# SCH_teency_2021-08-24.net
KiCad netlist of a schematic drawn in EasyEDA
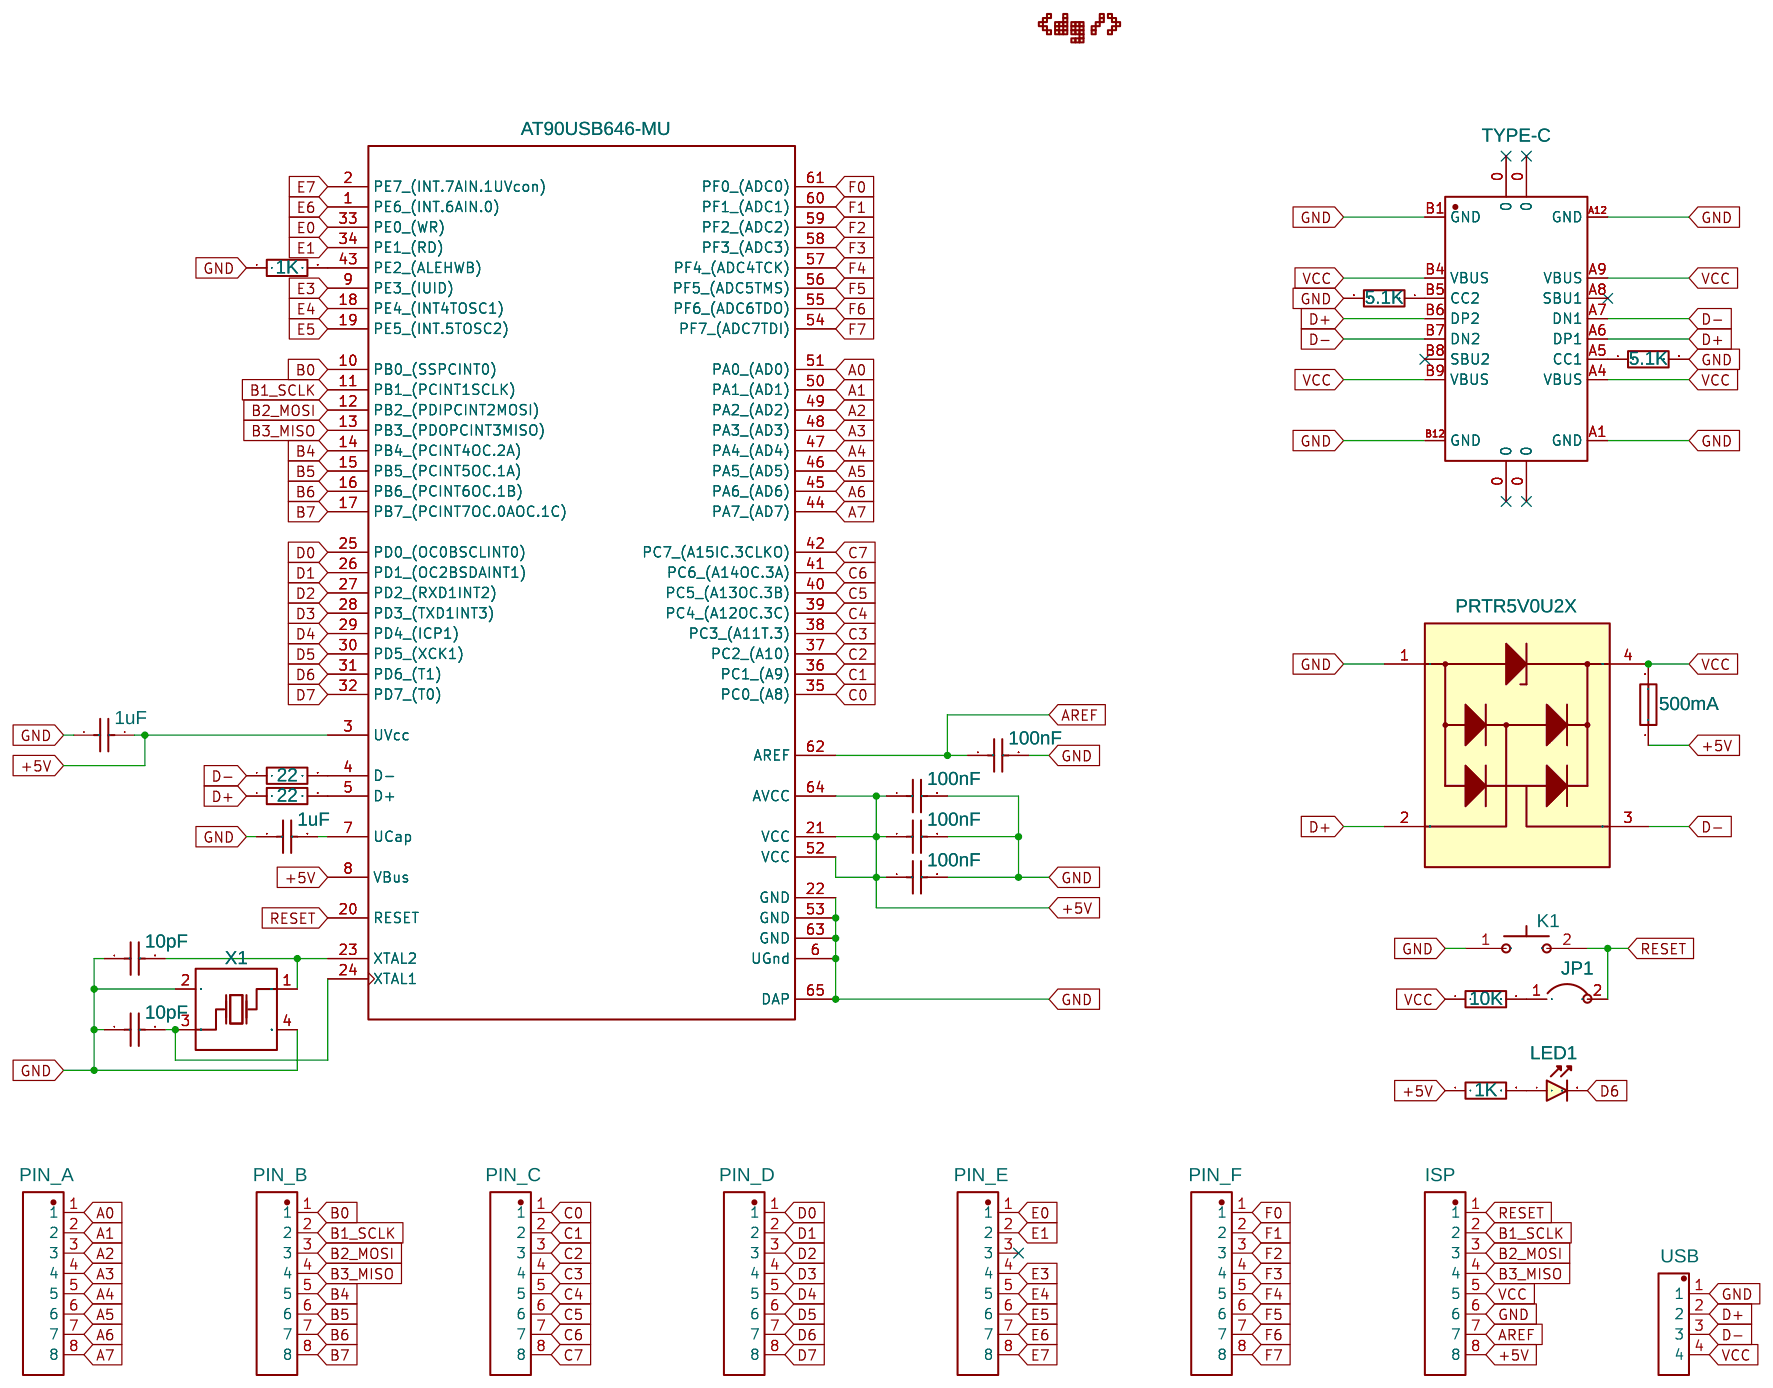
[diagram p0: schematic sheet]

(export (version "E")
  (design (tool "Eeschema 10.0.6"))
  (components
    (comp (ref "C1")
      (value "1uF")
      (fields
        (field (name "BOM_Manufacturer Part") "CL21B105KBFNNNE")
        (field (name "BOM_Supplier Part") "C28323")
      )
      (libsource (lib "") (part "CL21B105KBFNNNE"))
    )
    (comp (ref "C2")
      (value "100nF")
      (fields
        (field (name "BOM_Manufacturer Part") "CL21B104KBCNNNC")
        (field (name "BOM_Supplier Part") "C1711")
      )
      (libsource (lib "") (part "CC0805KRX7R9BB104"))
    )
    (comp (ref "C3")
      (value "100nF")
      (fields
        (field (name "BOM_Manufacturer Part") "CL21B104KBCNNNC")
        (field (name "BOM_Supplier Part") "C1711")
      )
      (libsource (lib "") (part "CC0805KRX7R9BB104"))
    )
    (comp (ref "C4")
      (value "1uF")
      (fields
        (field (name "BOM_Manufacturer Part") "CL21B105KBFNNNE")
        (field (name "BOM_Supplier Part") "C28323")
      )
      (libsource (lib "") (part "CL21B105KBFNNNE"))
    )
    (comp (ref "C5")
      (value "100nF")
      (fields
        (field (name "BOM_Manufacturer Part") "CL21B104KBCNNNC")
        (field (name "BOM_Supplier Part") "C1711")
      )
      (libsource (lib "") (part "CC0805KRX7R9BB104"))
    )
    (comp (ref "C6")
      (value "100nF")
      (fields
        (field (name "BOM_Manufacturer Part") "CL21B104KBCNNNC")
        (field (name "BOM_Supplier Part") "C1711")
      )
      (libsource (lib "") (part "CC0805KRX7R9BB104"))
    )
    (comp (ref "C7")
      (value "10pF")
      (fields
        (field (name "BOM_Manufacturer Part") "CL21C100JBANNNC")
        (field (name "BOM_Supplier Part") "C1785")
      )
      (libsource (lib "") (part "贴片电容-0805-10pF"))
    )
    (comp (ref "C8")
      (value "10pF")
      (fields
        (field (name "BOM_Manufacturer Part") "CL21C100JBANNNC")
        (field (name "BOM_Supplier Part") "C1785")
      )
      (libsource (lib "") (part "贴片电容-0805-10pF"))
    )
    (comp (ref "CN1")
      (value "TYPE-C")
      (fields
        (field (name "BOM_Manufacturer Part") "TYPE-C-31-M-12")
        (field (name "BOM_Supplier Part") "C165948")
      )
      (libsource (lib "") (part "TYPE-C-31-M-12"))
    )
    (comp (ref "F1")
      (value "500mA")
      (fields
        (field (name "BOM_Manufacturer Part") "MF-NSMF050-2")
        (field (name "BOM_Supplier Part") "C75464")
      )
      (libsource (lib "") (part "MF-NSMF050-2"))
    )
    (comp (ref "JP1") (value "JUMPER") (libsource (lib "") (part "JUMPER")))
    (comp (ref "K1")
      (value "3x6x2.5 Switch")
      (fields
        (field (name "BOM_Manufacturer Part") "1TS002E-2400-2500")
        (field (name "BOM_Supplier Part") "C319365")
      )
      (libsource (lib "") (part "1TS002E-2400-2500"))
    )
    (comp (ref "L1") (value "Logo") (libsource (lib "") (part "Logo")))
    (comp (ref "LED1") (value "0603 LED") (libsource (lib "") (part "0603 LED")))
    (comp (ref "P1") (value "PIN_A") (libsource (lib "") (part "2.54 8P")))
    (comp (ref "P2") (value "PIN_B") (libsource (lib "") (part "2.54 8P")))
    (comp (ref "P3") (value "PIN_C") (libsource (lib "") (part "2.54 8P")))
    (comp (ref "P4") (value "PIN_D") (libsource (lib "") (part "2.54 8P")))
    (comp (ref "P5") (value "PIN_E") (libsource (lib "") (part "2.54 8P")))
    (comp (ref "P6") (value "PIN_F") (libsource (lib "") (part "2.54 8P")))
    (comp (ref "P7") (value "ISP") (libsource (lib "") (part "2.54 8P")))
    (comp (ref "P8")
      (value "USB")
      (fields
        (field (name "BOM_Manufacturer Part") "210S-1*4P L=11.6MMGold-plated black")
        (field (name "BOM_Supplier Part") "C124378")
      )
      (libsource (lib "") (part "Lee_2.54排针-P2.54-4P"))
    )
    (comp (ref "R1")
      (value "1K")
      (fields
        (field (name "BOM_Manufacturer Part") "RC0805JR-071KL")
        (field (name "BOM_Supplier Part") "C100046")
      )
      (libsource (lib "") (part "TC0525F1001T5E"))
    )
    (comp (ref "R2")
      (value "5.1K")
      (fields
        (field (name "BOM_Manufacturer Part") "RC0805JR-075K1L")
        (field (name "BOM_Supplier Part") "C105874")
      )
      (libsource (lib "") (part "0805W8F5101T5E_1"))
    )
    (comp (ref "R3")
      (value "5.1K")
      (fields
        (field (name "BOM_Manufacturer Part") "RC0805JR-075K1L")
        (field (name "BOM_Supplier Part") "C105874")
      )
      (libsource (lib "") (part "0805W8F5101T5E"))
    )
    (comp (ref "R4")
      (value "22")
      (fields
        (field (name "BOM_Manufacturer Part") "RC0805JR-0722RL")
        (field (name "BOM_Supplier Part") "C108406")
      )
      (libsource (lib "") (part "0603WAF220JT5E"))
    )
    (comp (ref "R5")
      (value "22")
      (fields
        (field (name "BOM_Manufacturer Part") "RC0805JR-0722RL")
        (field (name "BOM_Supplier Part") "C108406")
      )
      (libsource (lib "") (part "0603WAF220JT5E"))
    )
    (comp (ref "R6")
      (value "10K")
      (fields
        (field (name "BOM_Manufacturer Part") "RC0805JR-0710KL")
        (field (name "BOM_Supplier Part") "C100047")
      )
      (libsource (lib "") (part "0805W8F1002T5E"))
    )
    (comp (ref "R7")
      (value "1K")
      (fields
        (field (name "BOM_Manufacturer Part") "RC0805JR-071KL")
        (field (name "BOM_Supplier Part") "C100046")
      )
      (libsource (lib "") (part "TC0525F1001T5E"))
    )
    (comp (ref "U1") (value "AT90USB646-MU") (libsource (lib "") (part "AT90USB646-MU")))
    (comp (ref "U2")
      (value "PRTR5V0U2X")
      (fields (field (name "BOM_Supplier Part") "C330092"))
      (libsource (lib "") (part "PRTR5V0U2X"))
    )
    (comp (ref "X1")
      (value "16MHz")
      (fields
        (field (name "BOM_Manufacturer Part") "X503216MSB4SI")
        (field (name "BOM_Supplier Part") "C112586")
      )
      (libsource (lib "") (part "X503216MSB4SI"))
    )
  )
  (nets
    (net (code "1") (name "+5V") (class "Default")
      (node (ref "C1") (pin "2") (pinfunction "2_2") (pintype "input"))
      (node (ref "C3") (pin "1") (pinfunction "1_1") (pintype "input"))
      (node (ref "C5") (pin "1") (pinfunction "1_1") (pintype "input"))
      (node (ref "C6") (pin "1") (pinfunction "1_1") (pintype "input"))
      (node (ref "F1") (pin "1") (pinfunction "1_1") (pintype "unspecified"))
      (node (ref "P7") (pin "8") (pinfunction "8_8") (pintype "unspecified"))
      (node (ref "R7") (pin "1") (pinfunction "1_1") (pintype "input"))
      (node (ref "U1") (pin "21") (pinfunction "VCC_21") (pintype "passive"))
      (node (ref "U1") (pin "3") (pinfunction "UVcc_3") (pintype "passive"))
      (node (ref "U1") (pin "52") (pinfunction "VCC_52") (pintype "passive"))
      (node (ref "U1") (pin "64") (pinfunction "AVCC_64") (pintype "passive"))
      (node (ref "U1") (pin "8") (pinfunction "VBus_8") (pintype "unspecified"))
    )
    (net (code "2") (name "A0") (class "Default")
      (node (ref "P1") (pin "1") (pinfunction "1_1") (pintype "unspecified"))
      (node (ref "U1") (pin "51") (pinfunction "PA0_(AD0)_51") (pintype "bidirectional"))
    )
    (net (code "3") (name "A1") (class "Default")
      (node (ref "P1") (pin "2") (pinfunction "2_2") (pintype "unspecified"))
      (node (ref "U1") (pin "50") (pinfunction "PA1_(AD1)_50") (pintype "bidirectional"))
    )
    (net (code "4") (name "A2") (class "Default")
      (node (ref "P1") (pin "3") (pinfunction "3_3") (pintype "unspecified"))
      (node (ref "U1") (pin "49") (pinfunction "PA2_(AD2)_49") (pintype "bidirectional"))
    )
    (net (code "5") (name "A3") (class "Default")
      (node (ref "P1") (pin "4") (pinfunction "4_4") (pintype "unspecified"))
      (node (ref "U1") (pin "48") (pinfunction "PA3_(AD3)_48") (pintype "bidirectional"))
    )
    (net (code "6") (name "A4") (class "Default")
      (node (ref "P1") (pin "5") (pinfunction "5_5") (pintype "unspecified"))
      (node (ref "U1") (pin "47") (pinfunction "PA4_(AD4)_47") (pintype "bidirectional"))
    )
    (net (code "7") (name "A5") (class "Default")
      (node (ref "P1") (pin "6") (pinfunction "6_6") (pintype "unspecified"))
      (node (ref "U1") (pin "46") (pinfunction "PA5_(AD5)_46") (pintype "bidirectional"))
    )
    (net (code "8") (name "A6") (class "Default")
      (node (ref "P1") (pin "7") (pinfunction "7_7") (pintype "unspecified"))
      (node (ref "U1") (pin "45") (pinfunction "PA6_(AD6)_45") (pintype "bidirectional"))
    )
    (net (code "9") (name "A7") (class "Default")
      (node (ref "P1") (pin "8") (pinfunction "8_8") (pintype "unspecified"))
      (node (ref "U1") (pin "44") (pinfunction "PA7_(AD7)_44") (pintype "bidirectional"))
    )
    (net (code "10") (name "AREF") (class "Default")
      (node (ref "C2") (pin "1") (pinfunction "1_1") (pintype "input"))
      (node (ref "P7") (pin "7") (pinfunction "7_7") (pintype "unspecified"))
      (node (ref "U1") (pin "62") (pinfunction "AREF_62") (pintype "unspecified"))
    )
    (net (code "11") (name "B0") (class "Default")
      (node (ref "P2") (pin "1") (pinfunction "1_1") (pintype "unspecified"))
      (node (ref "U1") (pin "10") (pinfunction "PB0_(SSPCINT0)_10") (pintype "bidirectional"))
    )
    (net (code "12") (name "B1_SCLK") (class "Default")
      (node (ref "P2") (pin "2") (pinfunction "2_2") (pintype "unspecified"))
      (node (ref "P7") (pin "2") (pinfunction "2_2") (pintype "unspecified"))
      (node (ref "U1") (pin "11") (pinfunction "PB1_(PCINT1SCLK)_11") (pintype "bidirectional"))
    )
    (net (code "13") (name "B2_MOSI") (class "Default")
      (node (ref "P2") (pin "3") (pinfunction "3_3") (pintype "unspecified"))
      (node (ref "P7") (pin "3") (pinfunction "3_3") (pintype "unspecified"))
      (node (ref "U1") (pin "12") (pinfunction "PB2_(PDIPCINT2MOSI)_12") (pintype "bidirectional"))
    )
    (net (code "14") (name "B3_MISO") (class "Default")
      (node (ref "P2") (pin "4") (pinfunction "4_4") (pintype "unspecified"))
      (node (ref "P7") (pin "4") (pinfunction "4_4") (pintype "unspecified"))
      (node (ref "U1") (pin "13") (pinfunction "PB3_(PDOPCINT3MISO)_13") (pintype "bidirectional"))
    )
    (net (code "15") (name "B4") (class "Default")
      (node (ref "P2") (pin "5") (pinfunction "5_5") (pintype "unspecified"))
      (node (ref "U1") (pin "14") (pinfunction "PB4_(PCINT4OC.2A)_14") (pintype "bidirectional"))
    )
    (net (code "16") (name "B5") (class "Default")
      (node (ref "P2") (pin "6") (pinfunction "6_6") (pintype "unspecified"))
      (node (ref "U1") (pin "15") (pinfunction "PB5_(PCINT5OC.1A)_15") (pintype "bidirectional"))
    )
    (net (code "17") (name "B6") (class "Default")
      (node (ref "P2") (pin "7") (pinfunction "7_7") (pintype "unspecified"))
      (node (ref "U1") (pin "16") (pinfunction "PB6_(PCINT6OC.1B)_16") (pintype "bidirectional"))
    )
    (net (code "18") (name "B7") (class "Default")
      (node (ref "P2") (pin "8") (pinfunction "8_8") (pintype "unspecified"))
      (node (ref "U1") (pin "17") (pinfunction "PB7_(PCINT7OC.0AOC.1C)_17") (pintype "bidirectional"))
    )
    (net (code "19") (name "C0") (class "Default")
      (node (ref "P3") (pin "1") (pinfunction "1_1") (pintype "unspecified"))
      (node (ref "U1") (pin "35") (pinfunction "PC0_(A8)_35") (pintype "bidirectional"))
    )
    (net (code "20") (name "C1") (class "Default")
      (node (ref "P3") (pin "2") (pinfunction "2_2") (pintype "unspecified"))
      (node (ref "U1") (pin "36") (pinfunction "PC1_(A9)_36") (pintype "bidirectional"))
    )
    (net (code "21") (name "C2") (class "Default")
      (node (ref "P3") (pin "3") (pinfunction "3_3") (pintype "unspecified"))
      (node (ref "U1") (pin "37") (pinfunction "PC2_(A10)_37") (pintype "bidirectional"))
    )
    (net (code "22") (name "C3") (class "Default")
      (node (ref "P3") (pin "4") (pinfunction "4_4") (pintype "unspecified"))
      (node (ref "U1") (pin "38") (pinfunction "PC3_(A11T.3)_38") (pintype "bidirectional"))
    )
    (net (code "23") (name "C4") (class "Default")
      (node (ref "P3") (pin "5") (pinfunction "5_5") (pintype "unspecified"))
      (node (ref "U1") (pin "39") (pinfunction "PC4_(A12OC.3C)_39") (pintype "bidirectional"))
    )
    (net (code "24") (name "C5") (class "Default")
      (node (ref "P3") (pin "6") (pinfunction "6_6") (pintype "unspecified"))
      (node (ref "U1") (pin "40") (pinfunction "PC5_(A13OC.3B)_40") (pintype "bidirectional"))
    )
    (net (code "25") (name "C6") (class "Default")
      (node (ref "P3") (pin "7") (pinfunction "7_7") (pintype "unspecified"))
      (node (ref "U1") (pin "41") (pinfunction "PC6_(A14OC.3A)_41") (pintype "bidirectional"))
    )
    (net (code "26") (name "C7") (class "Default")
      (node (ref "P3") (pin "8") (pinfunction "8_8") (pintype "unspecified"))
      (node (ref "U1") (pin "42") (pinfunction "PC7_(A15IC.3CLKO)_42") (pintype "bidirectional"))
    )
    (net (code "27") (name "D+") (class "Default")
      (node (ref "CN1") (pin "A6") (pinfunction "DP1_A6") (pintype "unspecified"))
      (node (ref "CN1") (pin "B6") (pinfunction "DP2_B6") (pintype "unspecified"))
      (node (ref "P8") (pin "2") (pinfunction "2_2") (pintype "unspecified"))
      (node (ref "R5") (pin "1") (pinfunction "1_1") (pintype "input"))
      (node (ref "U2") (pin "2") (pinfunction "IO1_2") (pintype "input"))
    )
    (net (code "28") (name "D-") (class "Default")
      (node (ref "CN1") (pin "A7") (pinfunction "DN1_A7") (pintype "unspecified"))
      (node (ref "CN1") (pin "B7") (pinfunction "DN2_B7") (pintype "unspecified"))
      (node (ref "P8") (pin "3") (pinfunction "3_3") (pintype "unspecified"))
      (node (ref "R4") (pin "1") (pinfunction "1_1") (pintype "input"))
      (node (ref "U2") (pin "3") (pinfunction "IO2_3") (pintype "input"))
    )
    (net (code "29") (name "D0") (class "Default")
      (node (ref "P4") (pin "1") (pinfunction "1_1") (pintype "unspecified"))
      (node (ref "U1") (pin "25") (pinfunction "PD0_(OC0BSCLINT0)_25") (pintype "bidirectional"))
    )
    (net (code "30") (name "D1") (class "Default")
      (node (ref "P4") (pin "2") (pinfunction "2_2") (pintype "unspecified"))
      (node (ref "U1") (pin "26") (pinfunction "PD1_(OC2BSDAINT1)_26") (pintype "bidirectional"))
    )
    (net (code "31") (name "D2") (class "Default")
      (node (ref "P4") (pin "3") (pinfunction "3_3") (pintype "unspecified"))
      (node (ref "U1") (pin "27") (pinfunction "PD2_(RXD1INT2)_27") (pintype "bidirectional"))
    )
    (net (code "32") (name "D3") (class "Default")
      (node (ref "P4") (pin "4") (pinfunction "4_4") (pintype "unspecified"))
      (node (ref "U1") (pin "28") (pinfunction "PD3_(TXD1INT3)_28") (pintype "bidirectional"))
    )
    (net (code "33") (name "D4") (class "Default")
      (node (ref "P4") (pin "5") (pinfunction "5_5") (pintype "unspecified"))
      (node (ref "U1") (pin "29") (pinfunction "PD4_(ICP1)_29") (pintype "bidirectional"))
    )
    (net (code "34") (name "D5") (class "Default")
      (node (ref "P4") (pin "6") (pinfunction "6_6") (pintype "unspecified"))
      (node (ref "U1") (pin "30") (pinfunction "PD5_(XCK1)_30") (pintype "bidirectional"))
    )
    (net (code "35") (name "D6") (class "Default")
      (node (ref "LED1") (pin "C") (pinfunction "C_C") (pintype "unspecified"))
      (node (ref "P4") (pin "7") (pinfunction "7_7") (pintype "unspecified"))
      (node (ref "U1") (pin "31") (pinfunction "PD6_(T1)_31") (pintype "bidirectional"))
    )
    (net (code "36") (name "D7") (class "Default")
      (node (ref "P4") (pin "8") (pinfunction "8_8") (pintype "unspecified"))
      (node (ref "U1") (pin "32") (pinfunction "PD7_(T0)_32") (pintype "bidirectional"))
    )
    (net (code "37") (name "E0") (class "Default")
      (node (ref "P5") (pin "1") (pinfunction "1_1") (pintype "unspecified"))
      (node (ref "U1") (pin "33") (pinfunction "PE0_(WR)_33") (pintype "bidirectional"))
    )
    (net (code "38") (name "E1") (class "Default")
      (node (ref "P5") (pin "2") (pinfunction "2_2") (pintype "unspecified"))
      (node (ref "U1") (pin "34") (pinfunction "PE1_(RD)_34") (pintype "bidirectional"))
    )
    (net (code "39") (name "E3") (class "Default")
      (node (ref "P5") (pin "4") (pinfunction "4_4") (pintype "unspecified"))
      (node (ref "U1") (pin "9") (pinfunction "PE3_(IUID)_9") (pintype "bidirectional"))
    )
    (net (code "40") (name "E4") (class "Default")
      (node (ref "P5") (pin "5") (pinfunction "5_5") (pintype "unspecified"))
      (node (ref "U1") (pin "18") (pinfunction "PE4_(INT4TOSC1)_18") (pintype "bidirectional"))
    )
    (net (code "41") (name "E5") (class "Default")
      (node (ref "P5") (pin "6") (pinfunction "6_6") (pintype "unspecified"))
      (node (ref "U1") (pin "19") (pinfunction "PE5_(INT.5TOSC2)_19") (pintype "bidirectional"))
    )
    (net (code "42") (name "E6") (class "Default")
      (node (ref "P5") (pin "7") (pinfunction "7_7") (pintype "unspecified"))
      (node (ref "U1") (pin "1") (pinfunction "PE6_(INT.6AIN.0)_1") (pintype "bidirectional"))
    )
    (net (code "43") (name "E7") (class "Default")
      (node (ref "P5") (pin "8") (pinfunction "8_8") (pintype "unspecified"))
      (node (ref "U1") (pin "2") (pinfunction "PE7_(INT.7AIN.1UVcon)_2") (pintype "bidirectional"))
    )
    (net (code "44") (name "F0") (class "Default")
      (node (ref "P6") (pin "1") (pinfunction "1_1") (pintype "unspecified"))
      (node (ref "U1") (pin "61") (pinfunction "PF0_(ADC0)_61") (pintype "bidirectional"))
    )
    (net (code "45") (name "F1") (class "Default")
      (node (ref "P6") (pin "2") (pinfunction "2_2") (pintype "unspecified"))
      (node (ref "U1") (pin "60") (pinfunction "PF1_(ADC1)_60") (pintype "bidirectional"))
    )
    (net (code "46") (name "F2") (class "Default")
      (node (ref "P6") (pin "3") (pinfunction "3_3") (pintype "unspecified"))
      (node (ref "U1") (pin "59") (pinfunction "PF2_(ADC2)_59") (pintype "bidirectional"))
    )
    (net (code "47") (name "F3") (class "Default")
      (node (ref "P6") (pin "4") (pinfunction "4_4") (pintype "unspecified"))
      (node (ref "U1") (pin "58") (pinfunction "PF3_(ADC3)_58") (pintype "bidirectional"))
    )
    (net (code "48") (name "F4") (class "Default")
      (node (ref "P6") (pin "5") (pinfunction "5_5") (pintype "unspecified"))
      (node (ref "U1") (pin "57") (pinfunction "PF4_(ADC4TCK)_57") (pintype "bidirectional"))
    )
    (net (code "49") (name "F5") (class "Default")
      (node (ref "P6") (pin "6") (pinfunction "6_6") (pintype "unspecified"))
      (node (ref "U1") (pin "56") (pinfunction "PF5_(ADC5TMS)_56") (pintype "bidirectional"))
    )
    (net (code "50") (name "F6") (class "Default")
      (node (ref "P6") (pin "7") (pinfunction "7_7") (pintype "unspecified"))
      (node (ref "U1") (pin "55") (pinfunction "PF6_(ADC6TDO)_55") (pintype "bidirectional"))
    )
    (net (code "51") (name "F7") (class "Default")
      (node (ref "P6") (pin "8") (pinfunction "8_8") (pintype "unspecified"))
      (node (ref "U1") (pin "54") (pinfunction "PF7_(ADC7TDI)_54") (pintype "bidirectional"))
    )
    (net (code "52") (name "GND") (class "Default")
      (node (ref "C1") (pin "1") (pinfunction "1_1") (pintype "input"))
      (node (ref "C2") (pin "2") (pinfunction "2_2") (pintype "input"))
      (node (ref "C3") (pin "2") (pinfunction "2_2") (pintype "input"))
      (node (ref "C4") (pin "1") (pinfunction "1_1") (pintype "input"))
      (node (ref "C5") (pin "2") (pinfunction "2_2") (pintype "input"))
      (node (ref "C6") (pin "2") (pinfunction "2_2") (pintype "input"))
      (node (ref "C7") (pin "1") (pinfunction "1_1") (pintype "input"))
      (node (ref "C8") (pin "1") (pinfunction "1_1") (pintype "input"))
      (node (ref "CN1") (pin "A1") (pinfunction "GND_A1") (pintype "unspecified"))
      (node (ref "CN1") (pin "A12") (pinfunction "GND_A12") (pintype "unspecified"))
      (node (ref "CN1") (pin "B1") (pinfunction "GND_B1") (pintype "unspecified"))
      (node (ref "CN1") (pin "B12") (pinfunction "GND_B12") (pintype "unspecified"))
      (node (ref "K1") (pin "1") (pinfunction "1_1") (pintype "unspecified"))
      (node (ref "P7") (pin "6") (pinfunction "6_6") (pintype "unspecified"))
      (node (ref "P8") (pin "1") (pinfunction "1_1") (pintype "unspecified"))
      (node (ref "R1") (pin "1") (pinfunction "1_1") (pintype "input"))
      (node (ref "R2") (pin "2") (pinfunction "2_2") (pintype "input"))
      (node (ref "R3") (pin "2") (pinfunction "2_2") (pintype "input"))
      (node (ref "U1") (pin "22") (pinfunction "GND_22") (pintype "passive"))
      (node (ref "U1") (pin "53") (pinfunction "GND_53") (pintype "passive"))
      (node (ref "U1") (pin "6") (pinfunction "UGnd_6") (pintype "passive"))
      (node (ref "U1") (pin "63") (pinfunction "GND_63") (pintype "passive"))
      (node (ref "U1") (pin "65") (pinfunction "DAP_65") (pintype "passive"))
      (node (ref "U2") (pin "1") (pinfunction "GND_1") (pintype "input"))
      (node (ref "X1") (pin "2") (pinfunction "GND_2") (pintype "unspecified"))
      (node (ref "X1") (pin "4") (pinfunction "GND_4") (pintype "unspecified"))
    )
    (net (code "53") (name "Net-(CN1-CC1)") (class "Default")
      (node (ref "CN1") (pin "A5") (pinfunction "CC1_A5") (pintype "unspecified"))
      (node (ref "R3") (pin "1") (pinfunction "1_1") (pintype "input"))
    )
    (net (code "54") (name "Net-(CN1-CC2)") (class "Default")
      (node (ref "CN1") (pin "B5") (pinfunction "CC2_B5") (pintype "unspecified"))
      (node (ref "R2") (pin "1") (pinfunction "1_1") (pintype "input"))
    )
    (net (code "55") (name "Net-(JP1-Pad1)") (class "Default")
      (node (ref "JP1") (pin "1") (pinfunction "1_1") (pintype "unspecified"))
      (node (ref "R6") (pin "2") (pinfunction "2_2") (pintype "input"))
    )
    (net (code "56") (name "Net-(LED1-PadA)") (class "Default")
      (node (ref "LED1") (pin "A") (pinfunction "A_A") (pintype "unspecified"))
      (node (ref "R7") (pin "2") (pinfunction "2_2") (pintype "input"))
    )
    (net (code "57") (name "Net-(U1-D+)") (class "Default")
      (node (ref "R5") (pin "2") (pinfunction "2_2") (pintype "input"))
      (node (ref "U1") (pin "5") (pinfunction "D+_5") (pintype "bidirectional"))
    )
    (net (code "58") (name "Net-(U1-D-)") (class "Default")
      (node (ref "R4") (pin "2") (pinfunction "2_2") (pintype "input"))
      (node (ref "U1") (pin "4") (pinfunction "D-_4") (pintype "bidirectional"))
    )
    (net (code "59") (name "Net-(U1-PE2_(ALEHWB))") (class "Default")
      (node (ref "R1") (pin "2") (pinfunction "2_2") (pintype "input"))
      (node (ref "U1") (pin "43") (pinfunction "PE2_(ALEHWB)_43") (pintype "bidirectional"))
    )
    (net (code "60") (name "Net-(U1-UCap)") (class "Default")
      (node (ref "C4") (pin "2") (pinfunction "2_2") (pintype "input"))
      (node (ref "U1") (pin "7") (pinfunction "UCap_7") (pintype "passive"))
    )
    (net (code "61") (name "Net-(U1-XTAL1)") (class "Default")
      (node (ref "C8") (pin "2") (pinfunction "2_2") (pintype "input"))
      (node (ref "U1") (pin "24") (pinfunction "XTAL1_24") (pintype "unspecified"))
      (node (ref "X1") (pin "3") (pinfunction "OSC2_3") (pintype "unspecified"))
    )
    (net (code "62") (name "Net-(U1-XTAL2)") (class "Default")
      (node (ref "C7") (pin "2") (pinfunction "2_2") (pintype "input"))
      (node (ref "U1") (pin "23") (pinfunction "XTAL2_23") (pintype "output"))
      (node (ref "X1") (pin "1") (pinfunction "OSC1_1") (pintype "unspecified"))
    )
    (net (code "63") (name "RESET") (class "Default")
      (node (ref "JP1") (pin "2") (pinfunction "2_2") (pintype "unspecified"))
      (node (ref "K1") (pin "2") (pinfunction "2_2") (pintype "unspecified"))
      (node (ref "P7") (pin "1") (pinfunction "1_1") (pintype "unspecified"))
      (node (ref "U1") (pin "20") (pinfunction "RESET_20") (pintype "unspecified"))
    )
    (net (code "64") (name "VCC") (class "Default")
      (node (ref "CN1") (pin "A4") (pinfunction "VBUS_A4") (pintype "unspecified"))
      (node (ref "CN1") (pin "A9") (pinfunction "VBUS_A9") (pintype "unspecified"))
      (node (ref "CN1") (pin "B4") (pinfunction "VBUS_B4") (pintype "unspecified"))
      (node (ref "CN1") (pin "B9") (pinfunction "VBUS_B9") (pintype "unspecified"))
      (node (ref "F1") (pin "2") (pinfunction "2_2") (pintype "unspecified"))
      (node (ref "P7") (pin "5") (pinfunction "5_5") (pintype "unspecified"))
      (node (ref "P8") (pin "4") (pinfunction "4_4") (pintype "unspecified"))
      (node (ref "R6") (pin "1") (pinfunction "1_1") (pintype "input"))
      (node (ref "U2") (pin "4") (pinfunction "VCC_4") (pintype "input"))
    )
    (net (code "65") (name "unconnected-(CN1-Pad0)") (class "Default")
      (node (ref "CN1") (pin "0") (pinfunction "0_0") (pintype "unspecified+no_connect"))
    )
    (net (code "66") (name "unconnected-(CN1-Pad0)_1") (class "Default")
      (node (ref "CN1") (pin "0") (pinfunction "0_0") (pintype "unspecified+no_connect"))
    )
    (net (code "67") (name "unconnected-(CN1-Pad0)_2") (class "Default")
      (node (ref "CN1") (pin "0") (pinfunction "0_0") (pintype "unspecified+no_connect"))
    )
    (net (code "68") (name "unconnected-(CN1-Pad0)_3") (class "Default")
      (node (ref "CN1") (pin "0") (pinfunction "0_0") (pintype "unspecified+no_connect"))
    )
    (net (code "69") (name "unconnected-(CN1-SBU1-PadA8)") (class "Default")
      (node (ref "CN1") (pin "A8") (pinfunction "SBU1_A8") (pintype "unspecified+no_connect"))
    )
    (net (code "70") (name "unconnected-(CN1-SBU2-PadB8)") (class "Default")
      (node (ref "CN1") (pin "B8") (pinfunction "SBU2_B8") (pintype "unspecified+no_connect"))
    )
    (net (code "71") (name "unconnected-(P5-Pad3)") (class "Default")
      (node (ref "P5") (pin "3") (pinfunction "3_3") (pintype "unspecified+no_connect"))
    )
  )
)
